# MotherBoard_v20.net
KiCad netlist of a schematic drawn in EAGLE
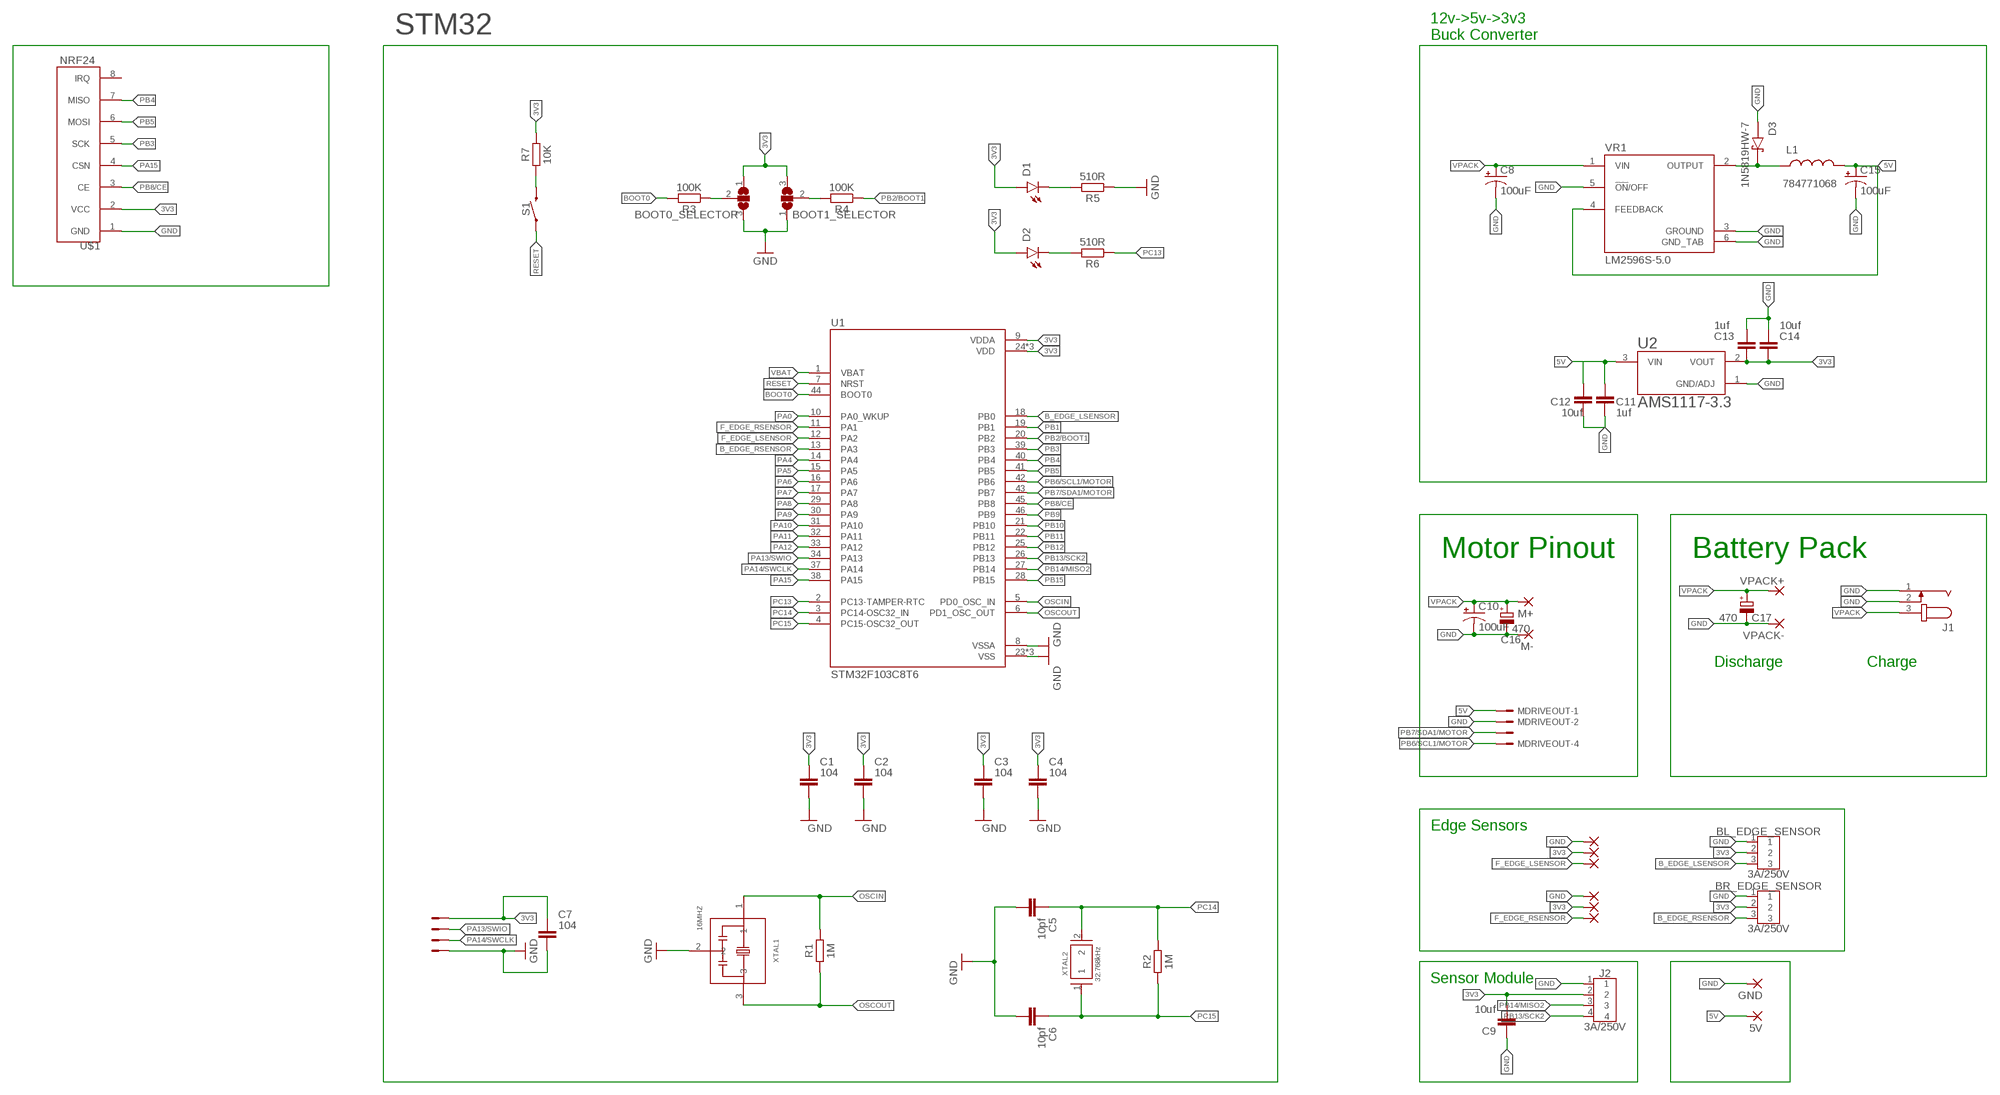
[diagram p0: schematic, sheet 1]

(export (version "E")
  (design (tool "Eeschema 10.0.6"))
  (components
    (comp (ref "5V")
      (value "WIREPADSMD5-1,8")
      (footprint "eagle-import:5-1,8")
      (libsource (lib "eagle-import") (part "WIREPADSMD5-1,8"))
    )
    (comp (ref "BL_EDGE_SENSOR")
      (value "3A/250V")
      (footprint "eagle-import:B3B-XH-A")
      (fields
        (field (name "MANUFACTURER") "JST (XH connector)")
        (field (name "MPN") "B3B-XH-A")
        (field (name "SPICEPREFIX") "J")
      )
      (libsource (lib "eagle-import") (part "B3B-XH-A"))
    )
    (comp (ref "BOOT0_SELECTOR")
      (value "SJ2W")
      (footprint "eagle-import:SJ_2")
      (libsource (lib "eagle-import") (part "SJ2W"))
    )
    (comp (ref "BOOT1_SELECTOR")
      (value "SJ2W")
      (footprint "eagle-import:SJ_2")
      (libsource (lib "eagle-import") (part "SJ2W"))
    )
    (comp (ref "BR_EDGE_SENSOR")
      (value "3A/250V")
      (footprint "eagle-import:B3B-XH-A")
      (fields
        (field (name "MANUFACTURER") "JST (XH connector)")
        (field (name "MPN") "B3B-XH-A")
        (field (name "SPICEPREFIX") "J")
      )
      (libsource (lib "eagle-import") (part "B3B-XH-A"))
    )
    (comp (ref "C1")
      (value "104")
      (footprint "eagle-import:CAPC1608X85")
      (libsource (lib "eagle-import") (part "CCHIP-0603(1608-METRIC)_"))
    )
    (comp (ref "C2")
      (value "104")
      (footprint "eagle-import:CAPC1608X85")
      (libsource (lib "eagle-import") (part "CCHIP-0603(1608-METRIC)_"))
    )
    (comp (ref "C3")
      (value "104")
      (footprint "eagle-import:CAPC1608X85")
      (libsource (lib "eagle-import") (part "CCHIP-0603(1608-METRIC)_"))
    )
    (comp (ref "C4")
      (value "104")
      (footprint "eagle-import:CAPC1608X85")
      (libsource (lib "eagle-import") (part "CCHIP-0603(1608-METRIC)_"))
    )
    (comp (ref "C5")
      (value "10pf")
      (footprint "eagle-import:CAPC1608X85")
      (libsource (lib "eagle-import") (part "CCHIP-0603(1608-METRIC)_"))
    )
    (comp (ref "C6")
      (value "10pf")
      (footprint "eagle-import:CAPC1608X85")
      (libsource (lib "eagle-import") (part "CCHIP-0603(1608-METRIC)_"))
    )
    (comp (ref "C7")
      (value "104")
      (footprint "eagle-import:CAPC1608X85")
      (libsource (lib "eagle-import") (part "CCHIP-0603(1608-METRIC)_"))
    )
    (comp (ref "C8")
      (value "100uF")
      (footprint "eagle-import:PANASONIC_D")
      (fields (field (name "SPICEPREFIX") "C"))
      (libsource (lib "eagle-import") (part "100UF-POLAR-25V-20%(ELEC)"))
    )
    (comp (ref "C9")
      (value "10uf")
      (footprint "eagle-import:CAPC1608X85")
      (libsource (lib "eagle-import") (part "Capacitor_16290819_CCHIP-0603(1608-METRIC)_"))
    )
    (comp (ref "C10")
      (value "100uF")
      (footprint "eagle-import:PANASONIC_D")
      (libsource (lib "eagle-import") (part "100UF-POLAR-25V-20%(ELEC)"))
    )
    (comp (ref "C11")
      (value "1uf")
      (footprint "eagle-import:CAPC1608X85")
      (libsource (lib "eagle-import") (part "Capacitor_16290819_CCHIP-0603(1608-METRIC)_"))
    )
    (comp (ref "C12")
      (value "10uf")
      (footprint "eagle-import:CAPC1608X85")
      (libsource (lib "eagle-import") (part "Capacitor_16290819_CCHIP-0603(1608-METRIC)_"))
    )
    (comp (ref "C13")
      (value "1uf")
      (footprint "eagle-import:CAPC1608X85")
      (libsource (lib "eagle-import") (part "Capacitor_16290819_CCHIP-0603(1608-METRIC)_"))
    )
    (comp (ref "C14")
      (value "10uf")
      (footprint "eagle-import:CAPC1608X85")
      (libsource (lib "eagle-import") (part "Capacitor_16290819_CCHIP-0603(1608-METRIC)_"))
    )
    (comp (ref "C15")
      (value "100uF")
      (footprint "eagle-import:PANASONIC_D")
      (fields (field (name "SPICEPREFIX") "C"))
      (libsource (lib "eagle-import") (part "100UF-POLAR-25V-20%(ELEC)"))
    )
    (comp (ref "C16")
      (value "470")
      (footprint "eagle-import:CAPPRD508W65D1000H1100B")
      (libsource (lib "eagle-import") (part "C-POLRADIAL-11MM-DIA_"))
    )
    (comp (ref "C17")
      (value "470")
      (footprint "eagle-import:CAPPRD508W65D1000H1100B")
      (libsource (lib "eagle-import") (part "C-POLRADIAL-11MM-DIA_"))
    )
    (comp (ref "D1")
      (value "LED_GREEN")
      (footprint "eagle-import:LEDC2012X105N_RND-G")
      (libsource (lib "eagle-import") (part "CHIP-ROUND-G_0805"))
    )
    (comp (ref "D2")
      (value "LED_GREEN")
      (footprint "eagle-import:LEDC2012X105N_RND-G")
      (libsource (lib "eagle-import") (part "CHIP-ROUND-G_0805"))
    )
    (comp (ref "D3")
      (value "1N5819HW-7")
      (footprint "eagle-import:SOD3715X145N")
      (fields (field (name "MF") "Diodes Inc.") (field (name "SPICEPREFIX") "D"))
      (libsource (lib "eagle-import") (part "1N5819HW-7"))
    )
    (comp (ref "GND")
      (value "WIREPADSMD5-1,8")
      (footprint "eagle-import:5-1,8")
      (libsource (lib "eagle-import") (part "WIREPADSMD5-1,8"))
    )
    (comp (ref "J-LINK-CONNECTOR")
      (value "SM04B-SSR-H-TB")
      (footprint "eagle-import:SM04B-SSR-H-TB")
      (libsource (lib "eagle-import") (part "SM04B-SSR-H-TB"))
    )
    (comp (ref "J1")
      (value "JACK-PLUG0")
      (footprint "eagle-import:SPC4077")
      (libsource (lib "eagle-import") (part "JACK-PLUG0"))
    )
    (comp (ref "J2")
      (value "3A/250V")
      (footprint "eagle-import:B4B-XH-A")
      (fields (field (name "MANUFACTURER") "JST (XH connector)") (field (name "MPN") "B4B-XH-A"))
      (libsource (lib "eagle-import") (part "B4B-XH-A"))
    )
    (comp (ref "L1")
      (value "784771068")
      (footprint "eagle-import:784771068")
      (fields
        (field (name "DIGIKEY_PART_NUMBER") "732-6770-2-ND")
        (field (name "MANUFACTURER") "Wurth Electronics Inc.")
        (field (name "SPICEPREFIX") "L")
        (field (name "CREATED_BY") "PCBLayout.com")
      )
      (libsource (lib "eagle-import") (part "784771068"))
    )
    (comp (ref "M+")
      (value "WIREPADSMD5-1,8")
      (footprint "eagle-import:5-1,8")
      (libsource (lib "eagle-import") (part "WIREPADSMD5-1,8"))
    )
    (comp (ref "M-")
      (value "WIREPADSMD5-1,8")
      (footprint "eagle-import:5-1,8")
      (libsource (lib "eagle-import") (part "WIREPADSMD5-1,8"))
    )
    (comp (ref "MDRIVEOUT")
      (value "SM04B-SSR-H-TB")
      (footprint "eagle-import:SM04B-SSR-H-TB")
      (libsource (lib "eagle-import") (part "SM04B-SSR-H-TB"))
    )
    (comp (ref "PAD1")
      (value "SMD2")
      (footprint "eagle-import:SMD1,27-2,54")
      (libsource (lib "eagle-import") (part "SMD2"))
    )
    (comp (ref "PAD2")
      (value "SMD2")
      (footprint "eagle-import:SMD1,27-2,54")
      (libsource (lib "eagle-import") (part "SMD2"))
    )
    (comp (ref "PAD3")
      (value "SMD2")
      (footprint "eagle-import:SMD1,27-2,54")
      (libsource (lib "eagle-import") (part "SMD2"))
    )
    (comp (ref "PAD4")
      (value "SMD2")
      (footprint "eagle-import:SMD1,27-2,54")
      (libsource (lib "eagle-import") (part "SMD2"))
    )
    (comp (ref "PAD5")
      (value "SMD2")
      (footprint "eagle-import:SMD1,27-2,54")
      (libsource (lib "eagle-import") (part "SMD2"))
    )
    (comp (ref "PAD6")
      (value "SMD2")
      (footprint "eagle-import:SMD1,27-2,54")
      (libsource (lib "eagle-import") (part "SMD2"))
    )
    (comp (ref "R1")
      (value "1M")
      (footprint "eagle-import:RESC1608X60")
      (libsource (lib "eagle-import") (part "RCHIP-0603(1608-METRIC)_"))
    )
    (comp (ref "R2")
      (value "1M")
      (footprint "eagle-import:RESC1608X60")
      (libsource (lib "eagle-import") (part "RCHIP-0603(1608-METRIC)_"))
    )
    (comp (ref "R3")
      (value "100K")
      (footprint "eagle-import:RESC1608X60")
      (libsource (lib "eagle-import") (part "RCHIP-0603(1608-METRIC)_"))
    )
    (comp (ref "R4")
      (value "100K")
      (footprint "eagle-import:RESC1608X60")
      (libsource (lib "eagle-import") (part "RCHIP-0603(1608-METRIC)_"))
    )
    (comp (ref "R5")
      (value "510R")
      (footprint "eagle-import:RESC1608X60")
      (libsource (lib "eagle-import") (part "RCHIP-0603(1608-METRIC)_"))
    )
    (comp (ref "R6")
      (value "510R")
      (footprint "eagle-import:RESC1608X60")
      (libsource (lib "eagle-import") (part "RCHIP-0603(1608-METRIC)_"))
    )
    (comp (ref "R7")
      (value "10K")
      (footprint "eagle-import:RESC1608X60")
      (libsource (lib "eagle-import") (part "RCHIP-0603(1608-METRIC)_"))
    )
    (comp (ref "S1")
      (value "MOMENTARY-SWITCH-SPST-SMD-6.0X3.5MM")
      (footprint "eagle-import:TACTILE_SWITCH_SMD_6.0X3.5MM")
      (libsource (lib "eagle-import") (part "MOMENTARY-SWITCH-SPST-SMD-6.0X3.5MM"))
    )
    (comp (ref "U$1")
      (value "NRF24")
      (footprint "eagle-import:NRF24")
      (libsource (lib "eagle-import") (part "NRF24"))
    )
    (comp (ref "U1")
      (value "STM32F103C8T6")
      (footprint "eagle-import:QFP50P900X900X160-48N")
      (fields (field (name "MF") "STMicroelectronics"))
      (libsource (lib "eagle-import") (part "STM32F103C8T6"))
    )
    (comp (ref "U2")
      (value "AMS1117-3.3")
      (footprint "eagle-import:SOT229P700X180-4N")
      (fields (field (name "MF") "Advanced Monolithic Systems") (field (name "SPICEPREFIX") "U"))
      (libsource (lib "eagle-import") (part "AMS1117-3.3"))
    )
    (comp (ref "VPACK+")
      (value "SMD5")
      (footprint "eagle-import:SMD2,54-5,08")
      (libsource (lib "eagle-import") (part "SMD5"))
    )
    (comp (ref "VPACK-")
      (value "SMD5")
      (footprint "eagle-import:SMD2,54-5,08")
      (libsource (lib "eagle-import") (part "SMD5"))
    )
    (comp (ref "VR1")
      (value "LM2596S-5.0")
      (footprint "eagle-import:TO170P1524X483-6N")
      (fields (field (name "MF") "Texas Instruments") (field (name "SPICEPREFIX") "X"))
      (libsource (lib "eagle-import") (part "LM2596S-5.0"))
    )
    (comp (ref "XTAL1")
      (value "16MHZ")
      (footprint "eagle-import:OSC_CSTCE8M00G55-R0")
      (fields (field (name "MANUFACTURER") "Murata Electronics") (field (name "MPN") "CSTCE16M0V53-R0"))
      (libsource (lib "eagle-import") (part "CSTCEFREQUENCY_16MHZ"))
    )
    (comp (ref "XTAL2")
      (value "32.768kHz")
      (footprint "eagle-import:XTAL_ABS07-32.768KHZ-T")
      (fields (field (name "MANUFACTURER") "Abracon LLC") (field (name "MPN") "ABS07-32.768KHZ-T "))
      (libsource (lib "eagle-import") (part "ABSO7"))
    )
  )
  (nets
    (net (code "2") (name "3V3") (class "Default")
      (node (ref "BL_EDGE_SENSOR") (pin "2") (pinfunction "2_2") (pintype "bidirectional"))
      (node (ref "BOOT0_SELECTOR") (pin "1") (pinfunction "1_1") (pintype "passive"))
      (node (ref "BOOT1_SELECTOR") (pin "3") (pinfunction "3_3") (pintype "passive"))
      (node (ref "BR_EDGE_SENSOR") (pin "2") (pinfunction "2_2") (pintype "bidirectional"))
      (node (ref "C1") (pin "1") (pinfunction "1_1") (pintype "passive"))
      (node (ref "C13") (pin "2") (pinfunction "2_2") (pintype "passive"))
      (node (ref "C14") (pin "2") (pinfunction "2_2") (pintype "passive"))
      (node (ref "C2") (pin "1") (pinfunction "1_1") (pintype "passive"))
      (node (ref "C3") (pin "1") (pinfunction "1_1") (pintype "passive"))
      (node (ref "C4") (pin "1") (pinfunction "1_1") (pintype "passive"))
      (node (ref "C7") (pin "1") (pinfunction "1_1") (pintype "passive"))
      (node (ref "C9") (pin "2") (pinfunction "2_2") (pintype "passive"))
      (node (ref "D1") (pin "A") (pinfunction "A_A") (pintype "passive"))
      (node (ref "D2") (pin "A") (pinfunction "A_A") (pintype "passive"))
      (node (ref "J-LINK-CONNECTOR") (pin "4") (pinfunction "S_4") (pintype "passive"))
      (node (ref "J2") (pin "2") (pinfunction "2_2") (pintype "bidirectional"))
      (node (ref "PAD2") (pin "1") (pinfunction "P_1") (pintype "passive"))
      (node (ref "PAD5") (pin "1") (pinfunction "P_1") (pintype "passive"))
      (node (ref "R7") (pin "2") (pinfunction "2_2") (pintype "passive"))
      (node (ref "U$1") (pin "2") (pinfunction "VCC_2") (pintype "bidirectional"))
      (node (ref "U1") (pin "24") (pinfunction "VDD_24") (pintype "power_in"))
      (node (ref "U1") (pin "36") (pinfunction "VDD_36") (pintype "power_in"))
      (node (ref "U1") (pin "48") (pinfunction "VDD_48") (pintype "power_in"))
      (node (ref "U1") (pin "9") (pinfunction "VDDA_9") (pintype "power_in"))
      (node (ref "U2") (pin "2") (pinfunction "VOUT_2") (pintype "output"))
    )
    (net (code "3") (name "5V") (class "Default")
      (node (ref "5V") (pin "1") (pinfunction "P_1") (pintype "passive"))
      (node (ref "C11") (pin "1") (pinfunction "1_1") (pintype "passive"))
      (node (ref "C12") (pin "1") (pinfunction "1_1") (pintype "passive"))
      (node (ref "C15") (pin "+") (pinfunction "+_+") (pintype "passive"))
      (node (ref "L1") (pin "2") (pinfunction "2_2") (pintype "passive"))
      (node (ref "MDRIVEOUT") (pin "1") (pinfunction "S_1") (pintype "passive"))
      (node (ref "U2") (pin "3") (pinfunction "VIN_3") (pintype "input"))
      (node (ref "VR1") (pin "4") (pinfunction "FEEDBACK_4") (pintype "input"))
    )
    (net (code "4") (name "BOOT0") (class "Default")
      (node (ref "R3") (pin "2") (pinfunction "2_2") (pintype "passive"))
      (node (ref "U1") (pin "44") (pinfunction "BOOT0_44") (pintype "input"))
    )
    (net (code "5") (name "B_EDGE_LSENSOR") (class "Default")
      (node (ref "BL_EDGE_SENSOR") (pin "3") (pinfunction "3_3") (pintype "bidirectional"))
      (node (ref "U1") (pin "18") (pinfunction "PB0_18") (pintype "bidirectional"))
    )
    (net (code "6") (name "B_EDGE_RSENSOR") (class "Default")
      (node (ref "BR_EDGE_SENSOR") (pin "3") (pinfunction "3_3") (pintype "bidirectional"))
      (node (ref "U1") (pin "13") (pinfunction "PA3_13") (pintype "bidirectional"))
    )
    (net (code "7") (name "F_EDGE_LSENSOR") (class "Default")
      (node (ref "PAD3") (pin "1") (pinfunction "P_1") (pintype "passive"))
      (node (ref "U1") (pin "12") (pinfunction "PA2_12") (pintype "bidirectional"))
    )
    (net (code "8") (name "F_EDGE_RSENSOR") (class "Default")
      (node (ref "PAD6") (pin "1") (pinfunction "P_1") (pintype "passive"))
      (node (ref "U1") (pin "11") (pinfunction "PA1_11") (pintype "bidirectional"))
    )
    (net (code "9") (name "GND") (class "Default")
      (node (ref "BL_EDGE_SENSOR") (pin "1") (pinfunction "1_1") (pintype "bidirectional"))
      (node (ref "BOOT0_SELECTOR") (pin "3") (pinfunction "3_3") (pintype "passive"))
      (node (ref "BOOT1_SELECTOR") (pin "1") (pinfunction "1_1") (pintype "passive"))
      (node (ref "BR_EDGE_SENSOR") (pin "1") (pinfunction "1_1") (pintype "bidirectional"))
      (node (ref "C1") (pin "2") (pinfunction "2_2") (pintype "passive"))
      (node (ref "C10") (pin "-") (pinfunction "-_-") (pintype "passive"))
      (node (ref "C11") (pin "2") (pinfunction "2_2") (pintype "passive"))
      (node (ref "C12") (pin "2") (pinfunction "2_2") (pintype "passive"))
      (node (ref "C13") (pin "1") (pinfunction "1_1") (pintype "passive"))
      (node (ref "C14") (pin "1") (pinfunction "1_1") (pintype "passive"))
      (node (ref "C15") (pin "-") (pinfunction "-_-") (pintype "passive"))
      (node (ref "C16") (pin "2") (pinfunction "-_2") (pintype "passive"))
      (node (ref "C17") (pin "2") (pinfunction "-_2") (pintype "passive"))
      (node (ref "C2") (pin "2") (pinfunction "2_2") (pintype "passive"))
      (node (ref "C3") (pin "2") (pinfunction "2_2") (pintype "passive"))
      (node (ref "C4") (pin "2") (pinfunction "2_2") (pintype "passive"))
      (node (ref "C5") (pin "2") (pinfunction "2_2") (pintype "passive"))
      (node (ref "C6") (pin "2") (pinfunction "2_2") (pintype "passive"))
      (node (ref "C7") (pin "2") (pinfunction "2_2") (pintype "passive"))
      (node (ref "C8") (pin "-") (pinfunction "-_-") (pintype "passive"))
      (node (ref "C9") (pin "1") (pinfunction "1_1") (pintype "passive"))
      (node (ref "D3") (pin "A") (pinfunction "A_A") (pintype "passive"))
      (node (ref "GND") (pin "1") (pinfunction "P_1") (pintype "passive"))
      (node (ref "J-LINK-CONNECTOR") (pin "1") (pinfunction "S_1") (pintype "passive"))
      (node (ref "J1") (pin "1") (pinfunction "1_1") (pintype "passive"))
      (node (ref "J1") (pin "2") (pinfunction "2_2") (pintype "passive"))
      (node (ref "J2") (pin "1") (pinfunction "1_1") (pintype "bidirectional"))
      (node (ref "M-") (pin "1") (pinfunction "P_1") (pintype "passive"))
      (node (ref "MDRIVEOUT") (pin "2") (pinfunction "S_2") (pintype "passive"))
      (node (ref "PAD1") (pin "1") (pinfunction "P_1") (pintype "passive"))
      (node (ref "PAD4") (pin "1") (pinfunction "P_1") (pintype "passive"))
      (node (ref "R5") (pin "1") (pinfunction "1_1") (pintype "passive"))
      (node (ref "U$1") (pin "1") (pinfunction "GND_1") (pintype "bidirectional"))
      (node (ref "U1") (pin "23") (pinfunction "VSS_23") (pintype "power_in"))
      (node (ref "U1") (pin "35") (pinfunction "VSS_35") (pintype "power_in"))
      (node (ref "U1") (pin "47") (pinfunction "VSS_47") (pintype "power_in"))
      (node (ref "U1") (pin "8") (pinfunction "VSSA_8") (pintype "power_in"))
      (node (ref "U2") (pin "1") (pinfunction "GND/ADJ_1") (pintype "power_in"))
      (node (ref "VPACK-") (pin "1") (pinfunction "P_1") (pintype "passive"))
      (node (ref "VR1") (pin "3") (pinfunction "GROUND_3") (pintype "power_in"))
      (node (ref "VR1") (pin "5") (pinfunction "~{ON}/OFF_5") (pintype "input"))
      (node (ref "VR1") (pin "6") (pinfunction "GND_TAB_6") (pintype "power_in"))
      (node (ref "XTAL1") (pin "2") (pinfunction "2_2") (pintype "power_in"))
    )
    (net (code "10") (name "Net-(BOOT0_SELECTOR-Pad2)") (class "Default")
      (node (ref "BOOT0_SELECTOR") (pin "2") (pinfunction "2_2") (pintype "passive"))
      (node (ref "R3") (pin "1") (pinfunction "1_1") (pintype "passive"))
    )
    (net (code "11") (name "Net-(BOOT1_SELECTOR-Pad2)") (class "Default")
      (node (ref "BOOT1_SELECTOR") (pin "2") (pinfunction "2_2") (pintype "passive"))
      (node (ref "R4") (pin "2") (pinfunction "2_2") (pintype "passive"))
    )
    (net (code "12") (name "Net-(D1-PadC)") (class "Default")
      (node (ref "D1") (pin "C") (pinfunction "C_C") (pintype "passive"))
      (node (ref "R5") (pin "2") (pinfunction "2_2") (pintype "passive"))
    )
    (net (code "13") (name "Net-(D2-PadC)") (class "Default")
      (node (ref "D2") (pin "C") (pinfunction "C_C") (pintype "passive"))
      (node (ref "R6") (pin "2") (pinfunction "2_2") (pintype "passive"))
    )
    (net (code "14") (name "Net-(D3-K)") (class "Default")
      (node (ref "D3") (pin "C") (pinfunction "K_C") (pintype "passive"))
      (node (ref "L1") (pin "1") (pinfunction "1_1") (pintype "passive"))
      (node (ref "VR1") (pin "2") (pinfunction "OUTPUT_2") (pintype "output"))
    )
    (net (code "15") (name "Net-(R7-Pad1)") (class "Default")
      (node (ref "R7") (pin "1") (pinfunction "1_1") (pintype "passive"))
      (node (ref "S1") (pin "2") (pinfunction "2_2") (pintype "passive"))
    )
    (net (code "16") (name "OSCIN") (class "Default")
      (node (ref "R1") (pin "2") (pinfunction "2_2") (pintype "passive"))
      (node (ref "U1") (pin "5") (pinfunction "PD0_OSC_IN_5") (pintype "bidirectional"))
      (node (ref "XTAL1") (pin "1") (pinfunction "1_1") (pintype "passive"))
    )
    (net (code "17") (name "OSCOUT") (class "Default")
      (node (ref "R1") (pin "1") (pinfunction "1_1") (pintype "passive"))
      (node (ref "U1") (pin "6") (pinfunction "PD1_OSC_OUT_6") (pintype "bidirectional"))
      (node (ref "XTAL1") (pin "3") (pinfunction "3_3") (pintype "passive"))
    )
    (net (code "18") (name "PA0") (class "Default")
      (node (ref "U1") (pin "10") (pinfunction "PA0_WKUP_10") (pintype "bidirectional"))
    )
    (net (code "19") (name "PA4") (class "Default")
      (node (ref "U1") (pin "14") (pinfunction "PA4_14") (pintype "bidirectional"))
    )
    (net (code "20") (name "PA5") (class "Default")
      (node (ref "U1") (pin "15") (pinfunction "PA5_15") (pintype "bidirectional"))
    )
    (net (code "21") (name "PA6") (class "Default")
      (node (ref "U1") (pin "16") (pinfunction "PA6_16") (pintype "bidirectional"))
    )
    (net (code "22") (name "PA7") (class "Default")
      (node (ref "U1") (pin "17") (pinfunction "PA7_17") (pintype "bidirectional"))
    )
    (net (code "23") (name "PA8") (class "Default")
      (node (ref "U1") (pin "29") (pinfunction "PA8_29") (pintype "bidirectional"))
    )
    (net (code "24") (name "PA9") (class "Default")
      (node (ref "U1") (pin "30") (pinfunction "PA9_30") (pintype "bidirectional"))
    )
    (net (code "25") (name "PA10") (class "Default")
      (node (ref "U1") (pin "31") (pinfunction "PA10_31") (pintype "bidirectional"))
    )
    (net (code "26") (name "PA11") (class "Default")
      (node (ref "U1") (pin "32") (pinfunction "PA11_32") (pintype "bidirectional"))
    )
    (net (code "27") (name "PA12") (class "Default")
      (node (ref "U1") (pin "33") (pinfunction "PA12_33") (pintype "bidirectional"))
    )
    (net (code "28") (name "PA13{slash}SWIO") (class "Default")
      (node (ref "J-LINK-CONNECTOR") (pin "3") (pinfunction "S_3") (pintype "passive"))
      (node (ref "U1") (pin "34") (pinfunction "PA13_34") (pintype "bidirectional"))
    )
    (net (code "29") (name "PA14{slash}SWCLK") (class "Default")
      (node (ref "J-LINK-CONNECTOR") (pin "2") (pinfunction "S_2") (pintype "passive"))
      (node (ref "U1") (pin "37") (pinfunction "PA14_37") (pintype "bidirectional"))
    )
    (net (code "30") (name "PA15") (class "Default")
      (node (ref "U$1") (pin "4") (pinfunction "CSN_4") (pintype "bidirectional"))
      (node (ref "U1") (pin "38") (pinfunction "PA15_38") (pintype "bidirectional"))
    )
    (net (code "31") (name "PB1") (class "Default")
      (node (ref "U1") (pin "19") (pinfunction "PB1_19") (pintype "bidirectional"))
    )
    (net (code "32") (name "PB2{slash}BOOT1") (class "Default")
      (node (ref "R4") (pin "1") (pinfunction "1_1") (pintype "passive"))
      (node (ref "U1") (pin "20") (pinfunction "PB2_20") (pintype "bidirectional"))
    )
    (net (code "33") (name "PB3") (class "Default")
      (node (ref "U$1") (pin "5") (pinfunction "SCK_5") (pintype "bidirectional"))
      (node (ref "U1") (pin "39") (pinfunction "PB3_39") (pintype "bidirectional"))
    )
    (net (code "34") (name "PB4") (class "Default")
      (node (ref "U$1") (pin "7") (pinfunction "MISO_7") (pintype "bidirectional"))
      (node (ref "U1") (pin "40") (pinfunction "PB4_40") (pintype "bidirectional"))
    )
    (net (code "35") (name "PB5") (class "Default")
      (node (ref "U$1") (pin "6") (pinfunction "MOSI_6") (pintype "bidirectional"))
      (node (ref "U1") (pin "41") (pinfunction "PB5_41") (pintype "bidirectional"))
    )
    (net (code "36") (name "PB6{slash}SCL1{slash}MOTOR") (class "Default")
      (node (ref "MDRIVEOUT") (pin "4") (pinfunction "S_4") (pintype "passive"))
      (node (ref "U1") (pin "42") (pinfunction "PB6_42") (pintype "bidirectional"))
    )
    (net (code "37") (name "PB7{slash}SDA1{slash}MOTOR") (class "Default")
      (node (ref "MDRIVEOUT") (pin "3") (pinfunction "S_3") (pintype "passive"))
      (node (ref "U1") (pin "43") (pinfunction "PB7_43") (pintype "bidirectional"))
    )
    (net (code "38") (name "PB8{slash}CE") (class "Default")
      (node (ref "U$1") (pin "3") (pinfunction "CE_3") (pintype "bidirectional"))
      (node (ref "U1") (pin "45") (pinfunction "PB8_45") (pintype "bidirectional"))
    )
    (net (code "39") (name "PB9") (class "Default")
      (node (ref "U1") (pin "46") (pinfunction "PB9_46") (pintype "bidirectional"))
    )
    (net (code "40") (name "PB10") (class "Default")
      (node (ref "U1") (pin "21") (pinfunction "PB10_21") (pintype "bidirectional"))
    )
    (net (code "41") (name "PB11") (class "Default")
      (node (ref "U1") (pin "22") (pinfunction "PB11_22") (pintype "bidirectional"))
    )
    (net (code "42") (name "PB12") (class "Default")
      (node (ref "U1") (pin "25") (pinfunction "PB12_25") (pintype "bidirectional"))
    )
    (net (code "43") (name "PB13{slash}SCK2") (class "Default")
      (node (ref "J2") (pin "4") (pinfunction "4_4") (pintype "bidirectional"))
      (node (ref "U1") (pin "26") (pinfunction "PB13_26") (pintype "bidirectional"))
    )
    (net (code "44") (name "PB14{slash}MISO2") (class "Default")
      (node (ref "J2") (pin "3") (pinfunction "3_3") (pintype "bidirectional"))
      (node (ref "U1") (pin "27") (pinfunction "PB14_27") (pintype "bidirectional"))
    )
    (net (code "45") (name "PB15") (class "Default")
      (node (ref "U1") (pin "28") (pinfunction "PB15_28") (pintype "bidirectional"))
    )
    (net (code "46") (name "PC13") (class "Default")
      (node (ref "R6") (pin "1") (pinfunction "1_1") (pintype "passive"))
      (node (ref "U1") (pin "2") (pinfunction "PC13-TAMPER-RTC_2") (pintype "bidirectional"))
    )
    (net (code "47") (name "PC14") (class "Default")
      (node (ref "C5") (pin "1") (pinfunction "1_1") (pintype "passive"))
      (node (ref "R2") (pin "2") (pinfunction "2_2") (pintype "passive"))
      (node (ref "U1") (pin "3") (pinfunction "PC14-OSC32_IN_3") (pintype "bidirectional"))
      (node (ref "XTAL2") (pin "2") (pinfunction "2_2") (pintype "passive"))
    )
    (net (code "48") (name "PC15") (class "Default")
      (node (ref "C6") (pin "1") (pinfunction "1_1") (pintype "passive"))
      (node (ref "R2") (pin "1") (pinfunction "1_1") (pintype "passive"))
      (node (ref "U1") (pin "4") (pinfunction "PC15-OSC32_OUT_4") (pintype "bidirectional"))
      (node (ref "XTAL2") (pin "1") (pinfunction "1_1") (pintype "passive"))
    )
    (net (code "49") (name "RESET") (class "Default")
      (node (ref "S1") (pin "1") (pinfunction "1_1") (pintype "passive"))
      (node (ref "U1") (pin "7") (pinfunction "NRST_7") (pintype "input"))
    )
    (net (code "50") (name "VBAT") (class "Default")
      (node (ref "U1") (pin "1") (pinfunction "VBAT_1") (pintype "bidirectional"))
    )
    (net (code "51") (name "VPACK") (class "Default")
      (node (ref "C10") (pin "+") (pinfunction "+_+") (pintype "passive"))
      (node (ref "C16") (pin "1") (pinfunction "+_1") (pintype "passive"))
      (node (ref "C17") (pin "1") (pinfunction "+_1") (pintype "passive"))
      (node (ref "C8") (pin "+") (pinfunction "+_+") (pintype "passive"))
      (node (ref "J1") (pin "3") (pinfunction "3_3") (pintype "passive"))
      (node (ref "M+") (pin "1") (pinfunction "P_1") (pintype "passive"))
      (node (ref "VPACK+") (pin "1") (pinfunction "P_1") (pintype "passive"))
      (node (ref "VR1") (pin "1") (pinfunction "VIN_1") (pintype "input"))
    )
    (net (code "52") (name "unconnected-(U$1-IRQ-Pad8)") (class "Default")
      (node (ref "U$1") (pin "8") (pinfunction "IRQ_8") (pintype "bidirectional"))
    )
  )
)
